# mostekH.net
KiCad netlist of a schematic drawn in EAGLE
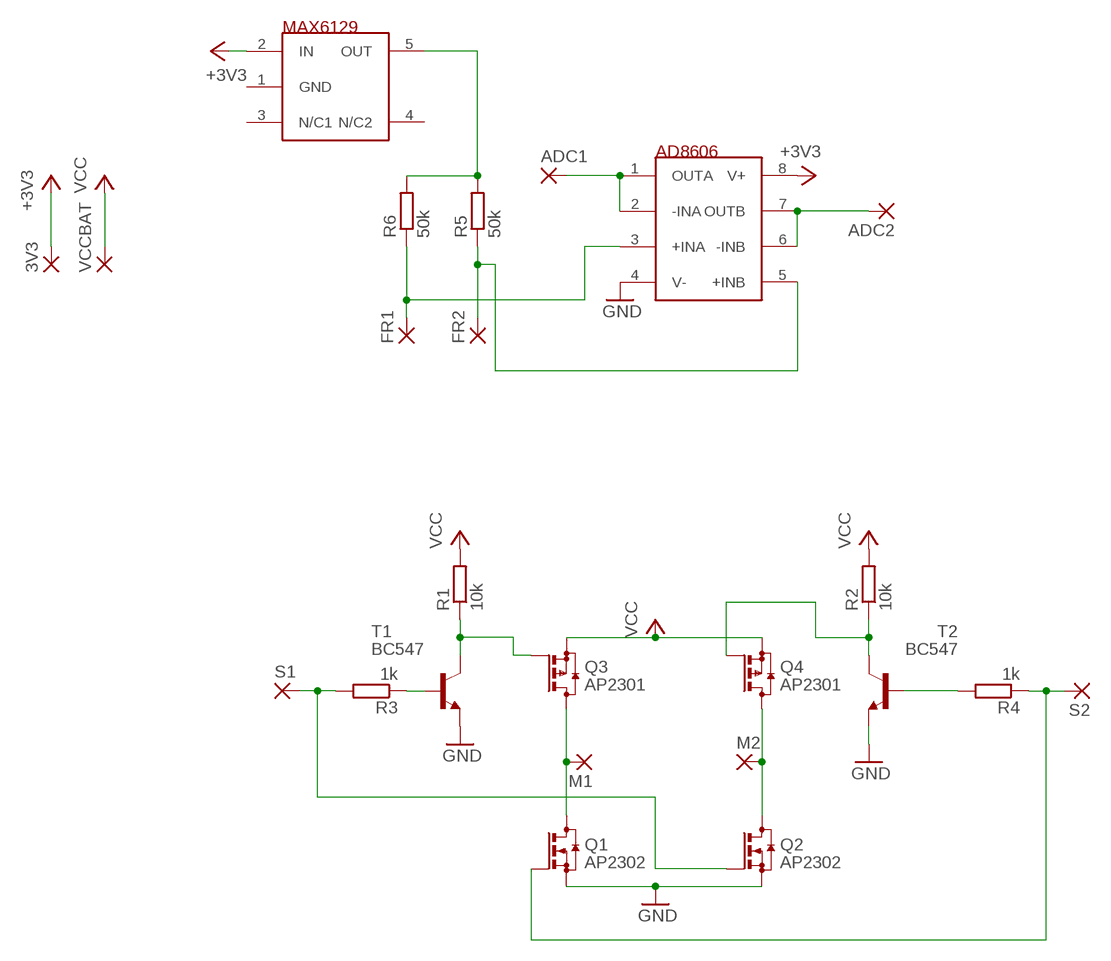
[diagram p0: schematic, sheet 1]

(export (version "E")
  (design (tool "Eeschema 10.0.6"))
  (components
    (comp (ref "3V3")
      (value "2,54/0,8")
      (footprint "eagle-import:2,54_0,8")
      (libsource (lib "eagle-import") (part "2,54/0,8"))
    )
    (comp (ref "ADC1")
      (value "2,54/0,8")
      (footprint "eagle-import:2,54_0,8")
      (libsource (lib "eagle-import") (part "2,54/0,8"))
    )
    (comp (ref "ADC2")
      (value "2,54/0,8")
      (footprint "eagle-import:2,54_0,8")
      (libsource (lib "eagle-import") (part "2,54/0,8"))
    )
    (comp (ref "FR1")
      (value "2,54/0,8")
      (footprint "eagle-import:2,54_0,8")
      (libsource (lib "eagle-import") (part "2,54/0,8"))
    )
    (comp (ref "FR2")
      (value "2,54/0,8")
      (footprint "eagle-import:2,54_0,8")
      (libsource (lib "eagle-import") (part "2,54/0,8"))
    )
    (comp (ref "M1")
      (value "2,54/0,8")
      (footprint "eagle-import:2,54_0,8")
      (libsource (lib "eagle-import") (part "2,54/0,8"))
    )
    (comp (ref "M2")
      (value "2,54/0,8")
      (footprint "eagle-import:2,54_0,8")
      (libsource (lib "eagle-import") (part "2,54/0,8"))
    )
    (comp (ref "Q1")
      (value "AP2302")
      (footprint "eagle-import:SOT23")
      (libsource (lib "eagle-import") (part "BSS123"))
    )
    (comp (ref "Q2")
      (value "AP2302")
      (footprint "eagle-import:SOT23")
      (libsource (lib "eagle-import") (part "BSS123"))
    )
    (comp (ref "Q3")
      (value "AP2301")
      (footprint "eagle-import:SOT23")
      (libsource (lib "eagle-import") (part "BSS84"))
    )
    (comp (ref "Q4")
      (value "AP2301")
      (footprint "eagle-import:SOT23")
      (libsource (lib "eagle-import") (part "BSS84"))
    )
    (comp (ref "R1")
      (value "10k")
      (footprint "eagle-import:M0805")
      (libsource (lib "eagle-import") (part "R-EU_M0805"))
    )
    (comp (ref "R2")
      (value "10k")
      (footprint "eagle-import:M0805")
      (libsource (lib "eagle-import") (part "R-EU_M0805"))
    )
    (comp (ref "R3")
      (value "1k")
      (footprint "eagle-import:M0805")
      (libsource (lib "eagle-import") (part "R-EU_M0805"))
    )
    (comp (ref "R4")
      (value "1k")
      (footprint "eagle-import:M0805")
      (libsource (lib "eagle-import") (part "R-EU_M0805"))
    )
    (comp (ref "R5")
      (value "50k")
      (footprint "eagle-import:M0805")
      (libsource (lib "eagle-import") (part "R-EU_M0805"))
    )
    (comp (ref "R6")
      (value "50k")
      (footprint "eagle-import:M0805")
      (libsource (lib "eagle-import") (part "R-EU_M0805"))
    )
    (comp (ref "S1")
      (value "2,54/0,8")
      (footprint "eagle-import:2,54_0,8")
      (libsource (lib "eagle-import") (part "2,54/0,8"))
    )
    (comp (ref "S2")
      (value "2,54/0,8")
      (footprint "eagle-import:2,54_0,8")
      (libsource (lib "eagle-import") (part "2,54/0,8"))
    )
    (comp (ref "T1")
      (value "BC547")
      (footprint "eagle-import:TO92")
      (libsource (lib "eagle-import") (part "BC547"))
    )
    (comp (ref "T2")
      (value "BC547")
      (footprint "eagle-import:TO92")
      (libsource (lib "eagle-import") (part "BC547"))
    )
    (comp (ref "U$1")
      (value "AD8606")
      (footprint "eagle-import:SOIC8")
      (libsource (lib "eagle-import") (part "AD8606"))
    )
    (comp (ref "U$2")
      (value "MAX6129")
      (footprint "eagle-import:SOT23-5L")
      (libsource (lib "eagle-import") (part "MAX6129"))
    )
    (comp (ref "VCCBAT")
      (value "2,54/0,8")
      (footprint "eagle-import:2,54_0,8")
      (libsource (lib "eagle-import") (part "2,54/0,8"))
    )
  )
  (nets
    (net (code "1") (name "+3V3") (class "Default")
      (node (ref "3V3") (pin "1") (pinfunction "P_1") (pintype "passive"))
      (node (ref "U$1") (pin "8") (pinfunction "V+_8") (pintype "bidirectional"))
      (node (ref "U$2") (pin "2") (pinfunction "IN_2") (pintype "bidirectional"))
    )
    (net (code "2") (name "GND") (class "Default")
      (node (ref "Q1") (pin "2") (pinfunction "S_2") (pintype "passive"))
      (node (ref "Q2") (pin "2") (pinfunction "S_2") (pintype "passive"))
      (node (ref "T1") (pin "1") (pinfunction "E_1") (pintype "passive"))
      (node (ref "T2") (pin "1") (pinfunction "E_1") (pintype "passive"))
      (node (ref "U$1") (pin "4") (pinfunction "V-_4") (pintype "bidirectional"))
    )
    (net (code "3") (name "Net-(ADC1-P)") (class "Default")
      (node (ref "ADC1") (pin "1") (pinfunction "P_1") (pintype "passive"))
      (node (ref "U$1") (pin "1") (pinfunction "OUTA_1") (pintype "bidirectional"))
      (node (ref "U$1") (pin "2") (pinfunction "-INA_2") (pintype "bidirectional"))
    )
    (net (code "4") (name "Net-(ADC2-P)") (class "Default")
      (node (ref "ADC2") (pin "1") (pinfunction "P_1") (pintype "passive"))
      (node (ref "U$1") (pin "6") (pinfunction "-INB_6") (pintype "bidirectional"))
      (node (ref "U$1") (pin "7") (pinfunction "OUTB_7") (pintype "bidirectional"))
    )
    (net (code "5") (name "Net-(FR1-P)") (class "Default")
      (node (ref "FR1") (pin "1") (pinfunction "P_1") (pintype "passive"))
      (node (ref "R6") (pin "1") (pinfunction "1_1") (pintype "passive"))
      (node (ref "U$1") (pin "3") (pinfunction "+INA_3") (pintype "bidirectional"))
    )
    (net (code "6") (name "Net-(FR2-P)") (class "Default")
      (node (ref "FR2") (pin "1") (pinfunction "P_1") (pintype "passive"))
      (node (ref "R5") (pin "1") (pinfunction "1_1") (pintype "passive"))
      (node (ref "U$1") (pin "5") (pinfunction "+INB_5") (pintype "bidirectional"))
    )
    (net (code "7") (name "Net-(M1-P)") (class "Default")
      (node (ref "M1") (pin "1") (pinfunction "P_1") (pintype "passive"))
      (node (ref "Q1") (pin "3") (pinfunction "D_3") (pintype "passive"))
      (node (ref "Q3") (pin "3") (pinfunction "D_3") (pintype "passive"))
    )
    (net (code "8") (name "Net-(M2-P)") (class "Default")
      (node (ref "M2") (pin "1") (pinfunction "P_1") (pintype "passive"))
      (node (ref "Q2") (pin "3") (pinfunction "D_3") (pintype "passive"))
      (node (ref "Q4") (pin "3") (pinfunction "D_3") (pintype "passive"))
    )
    (net (code "9") (name "Net-(Q1-G)") (class "Default")
      (node (ref "Q1") (pin "1") (pinfunction "G_1") (pintype "passive"))
      (node (ref "R4") (pin "1") (pinfunction "1_1") (pintype "passive"))
      (node (ref "S2") (pin "1") (pinfunction "P_1") (pintype "passive"))
    )
    (net (code "10") (name "Net-(Q2-G)") (class "Default")
      (node (ref "Q2") (pin "1") (pinfunction "G_1") (pintype "passive"))
      (node (ref "R3") (pin "2") (pinfunction "2_2") (pintype "passive"))
      (node (ref "S1") (pin "1") (pinfunction "P_1") (pintype "passive"))
    )
    (net (code "11") (name "Net-(Q3-G)") (class "Default")
      (node (ref "Q3") (pin "1") (pinfunction "G_1") (pintype "passive"))
      (node (ref "R1") (pin "1") (pinfunction "1_1") (pintype "passive"))
      (node (ref "T1") (pin "3") (pinfunction "C_3") (pintype "passive"))
    )
    (net (code "12") (name "Net-(Q4-G)") (class "Default")
      (node (ref "Q4") (pin "1") (pinfunction "G_1") (pintype "passive"))
      (node (ref "R2") (pin "1") (pinfunction "1_1") (pintype "passive"))
      (node (ref "T2") (pin "3") (pinfunction "C_3") (pintype "passive"))
    )
    (net (code "13") (name "Net-(T1-B)") (class "Default")
      (node (ref "R3") (pin "1") (pinfunction "1_1") (pintype "passive"))
      (node (ref "T1") (pin "2") (pinfunction "B_2") (pintype "passive"))
    )
    (net (code "14") (name "Net-(T2-B)") (class "Default")
      (node (ref "R4") (pin "2") (pinfunction "2_2") (pintype "passive"))
      (node (ref "T2") (pin "2") (pinfunction "B_2") (pintype "passive"))
    )
    (net (code "15") (name "Net-(U$2-OUT)") (class "Default")
      (node (ref "R5") (pin "2") (pinfunction "2_2") (pintype "passive"))
      (node (ref "R6") (pin "2") (pinfunction "2_2") (pintype "passive"))
      (node (ref "U$2") (pin "5") (pinfunction "OUT_5") (pintype "bidirectional"))
    )
    (net (code "16") (name "VCC") (class "Default")
      (node (ref "Q3") (pin "2") (pinfunction "S_2") (pintype "passive"))
      (node (ref "Q4") (pin "2") (pinfunction "S_2") (pintype "passive"))
      (node (ref "R1") (pin "2") (pinfunction "2_2") (pintype "passive"))
      (node (ref "R2") (pin "2") (pinfunction "2_2") (pintype "passive"))
      (node (ref "VCCBAT") (pin "1") (pinfunction "P_1") (pintype "passive"))
    )
    (net (code "17") (name "unconnected-(U$2-GND-Pad1)") (class "Default")
      (node (ref "U$2") (pin "1") (pinfunction "GND_1") (pintype "bidirectional"))
    )
    (net (code "18") (name "unconnected-(U$2-N{slash}C1-Pad3)") (class "Default")
      (node (ref "U$2") (pin "3") (pinfunction "N/C1_3") (pintype "bidirectional"))
    )
    (net (code "19") (name "unconnected-(U$2-N{slash}C2-Pad4)") (class "Default")
      (node (ref "U$2") (pin "4") (pinfunction "N/C2_4") (pintype "bidirectional"))
    )
  )
)
